# xDOT_Component.net
KiCad netlist of a schematic drawn in EAGLE
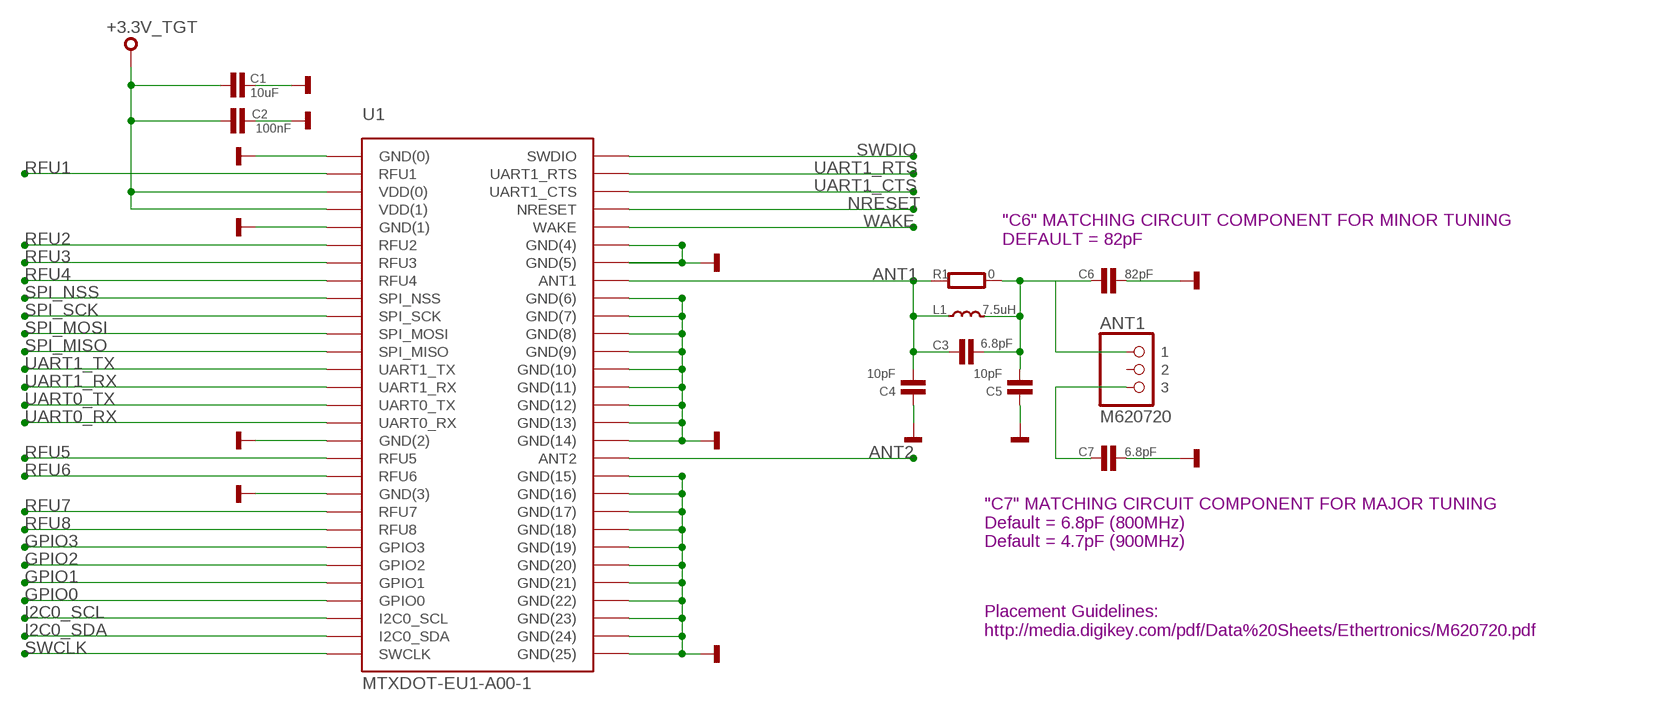
[diagram p0: schematic, sheet 1]

(export (version "E")
  (design (tool "Eeschema 10.0.6"))
  (components
    (comp (ref "ANT1")
      (value "M620720")
      (footprint "eagle-import:M620720")
      (fields (field (name "MF") "Ethertronics"))
      (libsource (lib "eagle-import") (part "M620720"))
    )
    (comp (ref "C1")
      (value "10uF")
      (footprint "eagle-import:0603")
      (libsource (lib "eagle-import") (part "CAPACITOR0603"))
    )
    (comp (ref "C2")
      (value "100nF")
      (footprint "eagle-import:0603")
      (libsource (lib "eagle-import") (part "CAPACITOR0603"))
    )
    (comp (ref "C3")
      (value "6.8pF")
      (footprint "eagle-import:0402")
      (libsource (lib "eagle-import") (part "CAPACITOR0402"))
    )
    (comp (ref "C4")
      (value "10pF")
      (footprint "eagle-import:0402")
      (libsource (lib "eagle-import") (part "CAPACITOR0402"))
    )
    (comp (ref "C5")
      (value "10pF")
      (footprint "eagle-import:0402")
      (libsource (lib "eagle-import") (part "CAPACITOR0402"))
    )
    (comp (ref "C6")
      (value "82pF")
      (footprint "eagle-import:0402")
      (libsource (lib "eagle-import") (part "CAPACITOR0402"))
    )
    (comp (ref "C7")
      (value "6.8pF")
      (footprint "eagle-import:0402")
      (libsource (lib "eagle-import") (part "CAPACITOR0402"))
    )
    (comp (ref "L1")
      (value "7.5uH")
      (footprint "eagle-import:0402")
      (libsource (lib "eagle-import") (part "INDUCTOR0402"))
    )
    (comp (ref "R1")
      (value "0")
      (footprint "eagle-import:0402")
      (libsource (lib "eagle-import") (part "RESISTOR0402"))
    )
    (comp (ref "U1")
      (value "MTXDOT-EU1-A00-1")
      (footprint "eagle-import:MTXDOT-EU1_NA1-A00-1")
      (fields (field (name "MF") "Multi-Tech Systems Inc."))
      (libsource (lib "eagle-import") (part "MTXDOT-EU1-A00-1"))
    )
  )
  (nets
    (net (code "1") (name "+3.3V_TGT") (class "Default")
      (node (ref "C1") (pin "1") (pinfunction "P$1_1") (pintype "passive"))
      (node (ref "C2") (pin "1") (pinfunction "P$1_1") (pintype "passive"))
      (node (ref "U1") (pin "P$3") (pinfunction "VDD(0)_P$3") (pintype "bidirectional"))
      (node (ref "U1") (pin "P$4") (pinfunction "VDD(1)_P$4") (pintype "bidirectional"))
    )
    (net (code "2") (name "/ANT1") (class "Default")
      (node (ref "C3") (pin "1") (pinfunction "P$1_1") (pintype "passive"))
      (node (ref "C4") (pin "2") (pinfunction "P$2_2") (pintype "passive"))
      (node (ref "L1") (pin "1") (pinfunction "P$1_1") (pintype "bidirectional"))
      (node (ref "R1") (pin "1") (pinfunction "P$1_1") (pintype "passive"))
      (node (ref "U1") (pin "P$37") (pinfunction "ANT1_P$37") (pintype "bidirectional"))
    )
    (net (code "3") (name "/ANT2") (class "Default")
      (node (ref "U1") (pin "P$47") (pinfunction "ANT2_P$47") (pintype "bidirectional"))
    )
    (net (code "4") (name "/GPIO0") (class "Default")
      (node (ref "U1") (pin "P$26") (pinfunction "GPIO0_P$26") (pintype "bidirectional"))
    )
    (net (code "5") (name "/GPIO1") (class "Default")
      (node (ref "U1") (pin "P$25") (pinfunction "GPIO1_P$25") (pintype "bidirectional"))
    )
    (net (code "6") (name "/GPIO2") (class "Default")
      (node (ref "U1") (pin "P$24") (pinfunction "GPIO2_P$24") (pintype "bidirectional"))
    )
    (net (code "7") (name "/GPIO3") (class "Default")
      (node (ref "U1") (pin "P$23") (pinfunction "GPIO3_P$23") (pintype "bidirectional"))
    )
    (net (code "8") (name "/I2C0_SCL") (class "Default")
      (node (ref "U1") (pin "P$27") (pinfunction "I2C0_SCL_P$27") (pintype "bidirectional"))
    )
    (net (code "9") (name "/I2C0_SDA") (class "Default")
      (node (ref "U1") (pin "P$28") (pinfunction "I2C0_SDA_P$28") (pintype "bidirectional"))
    )
    (net (code "10") (name "/NRESET") (class "Default")
      (node (ref "U1") (pin "P$33") (pinfunction "NRESET_P$33") (pintype "bidirectional"))
    )
    (net (code "11") (name "/RFU1") (class "Default")
      (node (ref "U1") (pin "P$2") (pinfunction "RFU1_P$2") (pintype "bidirectional"))
    )
    (net (code "12") (name "/RFU2") (class "Default")
      (node (ref "U1") (pin "P$6") (pinfunction "RFU2_P$6") (pintype "bidirectional"))
    )
    (net (code "13") (name "/RFU3") (class "Default")
      (node (ref "U1") (pin "P$7") (pinfunction "RFU3_P$7") (pintype "bidirectional"))
    )
    (net (code "14") (name "/RFU4") (class "Default")
      (node (ref "U1") (pin "P$8") (pinfunction "RFU4_P$8") (pintype "bidirectional"))
    )
    (net (code "15") (name "/RFU5") (class "Default")
      (node (ref "U1") (pin "P$18") (pinfunction "RFU5_P$18") (pintype "bidirectional"))
    )
    (net (code "16") (name "/RFU6") (class "Default")
      (node (ref "U1") (pin "P$19") (pinfunction "RFU6_P$19") (pintype "bidirectional"))
    )
    (net (code "17") (name "/RFU7") (class "Default")
      (node (ref "U1") (pin "P$21") (pinfunction "RFU7_P$21") (pintype "bidirectional"))
    )
    (net (code "18") (name "/RFU8") (class "Default")
      (node (ref "U1") (pin "P$22") (pinfunction "RFU8_P$22") (pintype "bidirectional"))
    )
    (net (code "19") (name "/SPI_MISO") (class "Default")
      (node (ref "U1") (pin "P$12") (pinfunction "SPI_MISO_P$12") (pintype "bidirectional"))
    )
    (net (code "20") (name "/SPI_MOSI") (class "Default")
      (node (ref "U1") (pin "P$11") (pinfunction "SPI_MOSI_P$11") (pintype "bidirectional"))
    )
    (net (code "21") (name "/SPI_NSS") (class "Default")
      (node (ref "U1") (pin "P$9") (pinfunction "SPI_NSS_P$9") (pintype "bidirectional"))
    )
    (net (code "22") (name "/SPI_SCK") (class "Default")
      (node (ref "U1") (pin "P$10") (pinfunction "SPI_SCK_P$10") (pintype "bidirectional"))
    )
    (net (code "23") (name "/SWCLK") (class "Default")
      (node (ref "U1") (pin "P$29") (pinfunction "SWCLK_P$29") (pintype "bidirectional"))
    )
    (net (code "24") (name "/SWDIO") (class "Default")
      (node (ref "U1") (pin "P$30") (pinfunction "SWDIO_P$30") (pintype "bidirectional"))
    )
    (net (code "25") (name "/UART0_RX") (class "Default")
      (node (ref "U1") (pin "P$16") (pinfunction "UART0_RX_P$16") (pintype "bidirectional"))
    )
    (net (code "26") (name "/UART0_TX") (class "Default")
      (node (ref "U1") (pin "P$15") (pinfunction "UART0_TX_P$15") (pintype "bidirectional"))
    )
    (net (code "27") (name "/UART1_CTS") (class "Default")
      (node (ref "U1") (pin "P$32") (pinfunction "UART1_CTS_P$32") (pintype "bidirectional"))
    )
    (net (code "28") (name "/UART1_RTS") (class "Default")
      (node (ref "U1") (pin "P$31") (pinfunction "UART1_RTS_P$31") (pintype "bidirectional"))
    )
    (net (code "29") (name "/UART1_RX") (class "Default")
      (node (ref "U1") (pin "P$14") (pinfunction "UART1_RX_P$14") (pintype "bidirectional"))
    )
    (net (code "30") (name "/UART1_TX") (class "Default")
      (node (ref "U1") (pin "P$13") (pinfunction "UART1_TX_P$13") (pintype "bidirectional"))
    )
    (net (code "31") (name "/WAKE") (class "Default")
      (node (ref "U1") (pin "P$34") (pinfunction "WAKE_P$34") (pintype "bidirectional"))
    )
    (net (code "32") (name "GND") (class "Default")
      (node (ref "C1") (pin "2") (pinfunction "P$2_2") (pintype "passive"))
      (node (ref "C2") (pin "2") (pinfunction "P$2_2") (pintype "passive"))
      (node (ref "C4") (pin "1") (pinfunction "P$1_1") (pintype "passive"))
      (node (ref "C5") (pin "1") (pinfunction "P$1_1") (pintype "passive"))
      (node (ref "C6") (pin "1") (pinfunction "P$1_1") (pintype "passive"))
      (node (ref "C7") (pin "1") (pinfunction "P$1_1") (pintype "passive"))
      (node (ref "U1") (pin "P$1") (pinfunction "GND(0)_P$1") (pintype "bidirectional"))
      (node (ref "U1") (pin "P$17") (pinfunction "GND(2)_P$17") (pintype "bidirectional"))
      (node (ref "U1") (pin "P$20") (pinfunction "GND(3)_P$20") (pintype "bidirectional"))
      (node (ref "U1") (pin "P$35") (pinfunction "GND(4)_P$35") (pintype "bidirectional"))
      (node (ref "U1") (pin "P$36") (pinfunction "GND(5)_P$36") (pintype "bidirectional"))
      (node (ref "U1") (pin "P$38") (pinfunction "GND(6)_P$38") (pintype "bidirectional"))
      (node (ref "U1") (pin "P$39") (pinfunction "GND(7)_P$39") (pintype "bidirectional"))
      (node (ref "U1") (pin "P$40") (pinfunction "GND(8)_P$40") (pintype "bidirectional"))
      (node (ref "U1") (pin "P$41") (pinfunction "GND(9)_P$41") (pintype "bidirectional"))
      (node (ref "U1") (pin "P$42") (pinfunction "GND(10)_P$42") (pintype "bidirectional"))
      (node (ref "U1") (pin "P$43") (pinfunction "GND(11)_P$43") (pintype "bidirectional"))
      (node (ref "U1") (pin "P$44") (pinfunction "GND(12)_P$44") (pintype "bidirectional"))
      (node (ref "U1") (pin "P$45") (pinfunction "GND(13)_P$45") (pintype "bidirectional"))
      (node (ref "U1") (pin "P$46") (pinfunction "GND(14)_P$46") (pintype "bidirectional"))
      (node (ref "U1") (pin "P$48") (pinfunction "GND(15)_P$48") (pintype "bidirectional"))
      (node (ref "U1") (pin "P$49") (pinfunction "GND(16)_P$49") (pintype "bidirectional"))
      (node (ref "U1") (pin "P$5") (pinfunction "GND(1)_P$5") (pintype "bidirectional"))
      (node (ref "U1") (pin "P$50") (pinfunction "GND(17)_P$50") (pintype "bidirectional"))
      (node (ref "U1") (pin "P$51") (pinfunction "GND(18)_P$51") (pintype "bidirectional"))
      (node (ref "U1") (pin "P$52") (pinfunction "GND(19)_P$52") (pintype "bidirectional"))
      (node (ref "U1") (pin "P$53") (pinfunction "GND(20)_P$53") (pintype "bidirectional"))
      (node (ref "U1") (pin "P$54") (pinfunction "GND(21)_P$54") (pintype "bidirectional"))
      (node (ref "U1") (pin "P$55") (pinfunction "GND(22)_P$55") (pintype "bidirectional"))
      (node (ref "U1") (pin "P$56") (pinfunction "GND(23)_P$56") (pintype "bidirectional"))
      (node (ref "U1") (pin "P$57") (pinfunction "GND(24)_P$57") (pintype "bidirectional"))
      (node (ref "U1") (pin "P$58") (pinfunction "GND(25)_P$58") (pintype "bidirectional"))
    )
    (net (code "33") (name "Net-(ANT1-1)") (class "Default")
      (node (ref "ANT1") (pin "P$1") (pinfunction "1_P$1") (pintype "passive"))
      (node (ref "C3") (pin "2") (pinfunction "P$2_2") (pintype "passive"))
      (node (ref "C5") (pin "2") (pinfunction "P$2_2") (pintype "passive"))
      (node (ref "C6") (pin "2") (pinfunction "P$2_2") (pintype "passive"))
      (node (ref "L1") (pin "2") (pinfunction "P$2_2") (pintype "bidirectional"))
      (node (ref "R1") (pin "2") (pinfunction "P$2_2") (pintype "passive"))
    )
    (net (code "34") (name "Net-(ANT1-3)") (class "Default")
      (node (ref "ANT1") (pin "P$3") (pinfunction "3_P$3") (pintype "passive"))
      (node (ref "C7") (pin "2") (pinfunction "P$2_2") (pintype "passive"))
    )
    (net (code "35") (name "unconnected-(ANT1-2-PadP$2)") (class "Default")
      (node (ref "ANT1") (pin "P$2") (pinfunction "2_P$2") (pintype "passive"))
    )
  )
)
